# Sheet1.net
KiCad netlist of a schematic drawn in Altium Designer
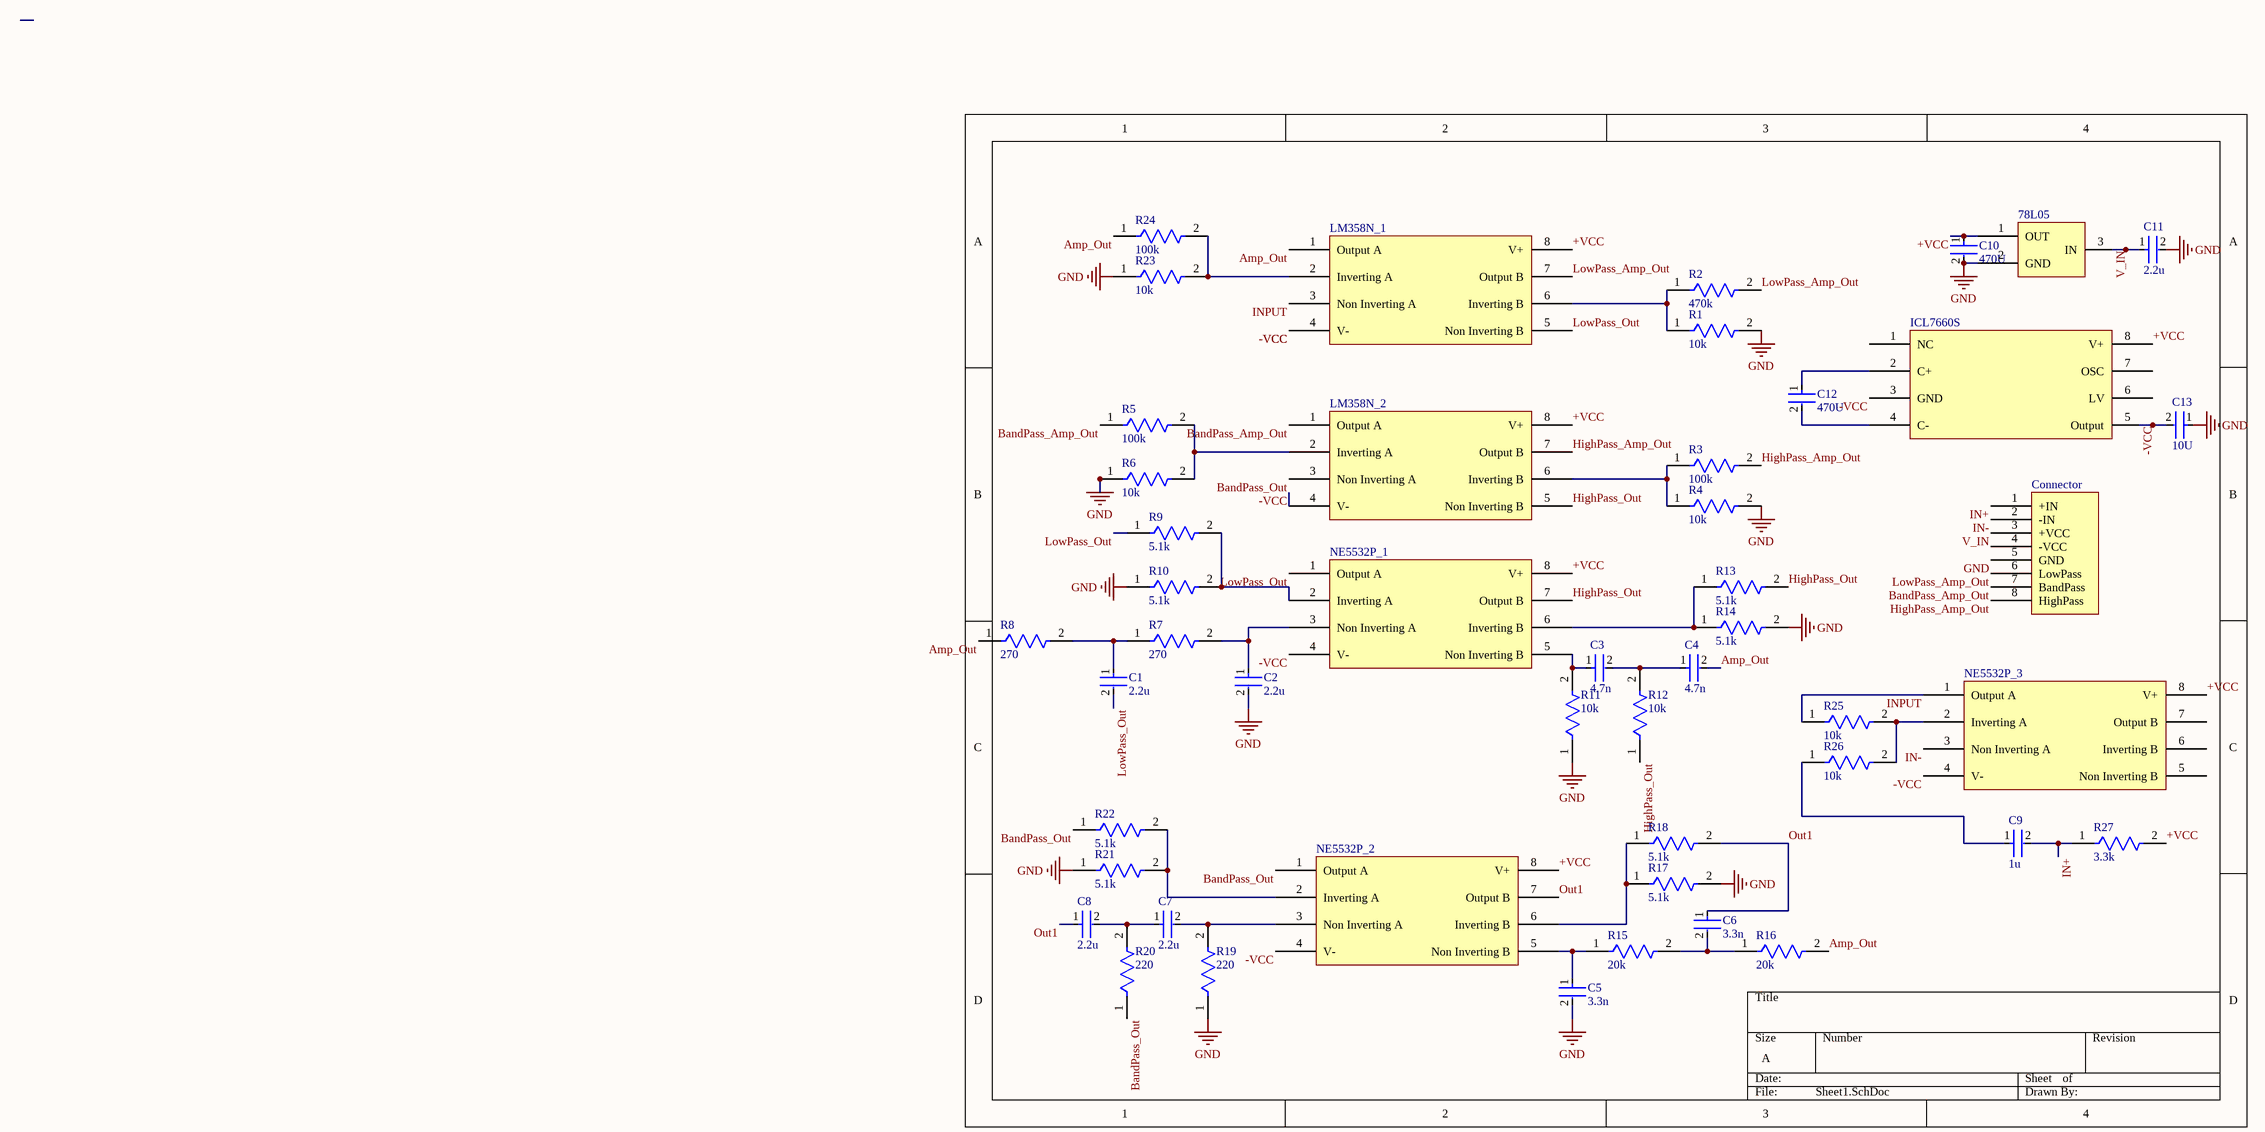
[diagram p0: Sheet1.SchDoc]

(export (version "E")
  (design (tool "Eeschema 10.0.6"))
  (components
    (comp (ref "78L05") (value "~") (footprint "78L05") (libsource (lib "Schlib1") (part "78L05")))
    (comp (ref "C1") (value "2.2u") (footprint "2.2u") (libsource (lib "Schlib1") (part "2.2u")))
    (comp (ref "C2") (value "2.2u") (footprint "2.2u") (libsource (lib "Schlib1") (part "2.2u")))
    (comp (ref "C3") (value "4.7n") (footprint "4.7n") (libsource (lib "Schlib1") (part "4.7n")))
    (comp (ref "C4") (value "4.7n") (footprint "4.7n") (libsource (lib "Schlib1") (part "4.7n")))
    (comp (ref "C5") (value "3.3n") (footprint "4.7n") (libsource (lib "Schlib1") (part "3.3n")))
    (comp (ref "C6") (value "3.3n") (footprint "4.7n") (libsource (lib "Schlib1") (part "3.3n")))
    (comp (ref "C7") (value "2.2u") (footprint "2.2u") (libsource (lib "Schlib1") (part "2.2u")))
    (comp (ref "C8") (value "2.2u") (footprint "2.2u") (libsource (lib "Schlib1") (part "2.2u")))
    (comp (ref "C9") (value "1u") (footprint "1u") (libsource (lib "Schlib1") (part "1u")))
    (comp (ref "C10") (value "470U") (footprint "470u") (libsource (lib "Schlib1") (part "470U")))
    (comp (ref "C11") (value "2.2u") (footprint "2.2u") (libsource (lib "Schlib1") (part "2.2u")))
    (comp (ref "C12") (value "470U") (footprint "470u") (libsource (lib "Schlib1") (part "470U")))
    (comp (ref "C13") (value "10U") (footprint "10u") (libsource (lib "Schlib1") (part "10U")))
    (comp (ref "Connector")
      (value "~")
      (footprint "Connector")
      (libsource (lib "Schlib1") (part "Connector"))
    )
    (comp (ref "ICL7660S") (value "~") (footprint "ICL7660S") (libsource (lib "Schlib1") (part "ICL7660S")))
    (comp (ref "LM358N_1") (value "~") (footprint "LM358N") (libsource (lib "Schlib1") (part "LM358N")))
    (comp (ref "LM358N_2") (value "~") (footprint "LM358N") (libsource (lib "Schlib1") (part "LM358N")))
    (comp (ref "NE5532P_1") (value "~") (footprint "NE5532P") (libsource (lib "Schlib1") (part "NE5532P")))
    (comp (ref "NE5532P_2") (value "~") (footprint "NE5532P") (libsource (lib "Schlib1") (part "NE5532P")))
    (comp (ref "NE5532P_3") (value "~") (footprint "NE5532P") (libsource (lib "Schlib1") (part "NE5532P")))
    (comp (ref "R1") (value "10k") (footprint "THT") (libsource (lib "Schlib1") (part "10k")))
    (comp (ref "R2") (value "470k") (footprint "THT") (libsource (lib "Schlib1") (part "470k")))
    (comp (ref "R3") (value "100k") (footprint "THT") (libsource (lib "Schlib1") (part "100k")))
    (comp (ref "R4") (value "10k") (footprint "THT") (libsource (lib "Schlib1") (part "10k")))
    (comp (ref "R5") (value "100k") (footprint "THT") (libsource (lib "Schlib1") (part "100k")))
    (comp (ref "R6") (value "10k") (footprint "THT") (libsource (lib "Schlib1") (part "10k")))
    (comp (ref "R7") (value "270") (footprint "THT") (libsource (lib "Schlib1") (part "270")))
    (comp (ref "R8") (value "270") (footprint "THT") (libsource (lib "Schlib1") (part "270")))
    (comp (ref "R9") (value "5.1k") (footprint "THT") (libsource (lib "Schlib1") (part "5.1k")))
    (comp (ref "R10") (value "5.1k") (footprint "THT") (libsource (lib "Schlib1") (part "5.1k")))
    (comp (ref "R11") (value "10k") (footprint "THT") (libsource (lib "Schlib1") (part "10k")))
    (comp (ref "R12") (value "10k") (footprint "THT") (libsource (lib "Schlib1") (part "10k")))
    (comp (ref "R13") (value "5.1k") (footprint "THT") (libsource (lib "Schlib1") (part "5.1k")))
    (comp (ref "R14") (value "5.1k") (footprint "THT") (libsource (lib "Schlib1") (part "5.1k")))
    (comp (ref "R15") (value "20k") (footprint "THT") (libsource (lib "Schlib1") (part "20k")))
    (comp (ref "R16") (value "20k") (footprint "THT") (libsource (lib "Schlib1") (part "20k")))
    (comp (ref "R17") (value "5.1k") (footprint "THT") (libsource (lib "Schlib1") (part "5.1k")))
    (comp (ref "R18") (value "5.1k") (footprint "THT") (libsource (lib "Schlib1") (part "5.1k")))
    (comp (ref "R19") (value "220") (footprint "THT") (libsource (lib "Schlib1") (part "220")))
    (comp (ref "R20") (value "220") (footprint "THT") (libsource (lib "Schlib1") (part "220")))
    (comp (ref "R21") (value "5.1k") (footprint "THT") (libsource (lib "Schlib1") (part "5.1k")))
    (comp (ref "R22") (value "5.1k") (footprint "THT") (libsource (lib "Schlib1") (part "5.1k")))
    (comp (ref "R23") (value "10k") (footprint "THT") (libsource (lib "Schlib1") (part "10k")))
    (comp (ref "R24") (value "100k") (footprint "THT") (libsource (lib "Schlib1") (part "100k")))
    (comp (ref "R25") (value "10k") (footprint "THT") (libsource (lib "Schlib1") (part "10k")))
    (comp (ref "R26") (value "10k") (footprint "THT") (libsource (lib "Schlib1") (part "10k")))
    (comp (ref "R27") (value "3.3k") (footprint "THT") (libsource (lib "Schlib1") (part "3.3k")))
  )
  (nets
    (net (code "1") (name "/+VCC") (class "Default")
      (node (ref "78L05") (pin "1") (pinfunction "OUT_1") (pintype "passive"))
      (node (ref "C10") (pin "1") (pinfunction "1_1") (pintype "passive"))
      (node (ref "ICL7660S") (pin "8") (pinfunction "V+_8") (pintype "passive"))
      (node (ref "LM358N_1") (pin "8") (pinfunction "V+_8") (pintype "passive"))
      (node (ref "LM358N_2") (pin "8") (pinfunction "V+_8") (pintype "passive"))
      (node (ref "NE5532P_1") (pin "8") (pinfunction "V+_8") (pintype "passive"))
      (node (ref "NE5532P_2") (pin "8") (pinfunction "V+_8") (pintype "passive"))
      (node (ref "NE5532P_3") (pin "8") (pinfunction "V+_8") (pintype "passive"))
      (node (ref "R27") (pin "2") (pinfunction "2_2") (pintype "passive"))
    )
    (net (code "2") (name "/-VCC") (class "Default")
      (node (ref "C13") (pin "2") (pinfunction "2_2") (pintype "passive"))
      (node (ref "ICL7660S") (pin "3") (pinfunction "GND_3") (pintype "passive"))
      (node (ref "ICL7660S") (pin "5") (pinfunction "Output_5") (pintype "passive"))
      (node (ref "LM358N_1") (pin "4") (pinfunction "V-_4") (pintype "passive"))
      (node (ref "LM358N_2") (pin "4") (pinfunction "V-_4") (pintype "passive"))
      (node (ref "NE5532P_1") (pin "4") (pinfunction "V-_4") (pintype "passive"))
      (node (ref "NE5532P_2") (pin "4") (pinfunction "V-_4") (pintype "passive"))
      (node (ref "NE5532P_3") (pin "4") (pinfunction "V-_4") (pintype "passive"))
    )
    (net (code "3") (name "/Amp_Out") (class "Default")
      (node (ref "C4") (pin "2") (pinfunction "2_2") (pintype "passive"))
      (node (ref "LM358N_1") (pin "1") (pinfunction "Output_A_1") (pintype "passive"))
      (node (ref "R16") (pin "2") (pinfunction "2_2") (pintype "passive"))
      (node (ref "R24") (pin "1") (pinfunction "1_1") (pintype "passive"))
      (node (ref "R8") (pin "1") (pinfunction "1_1") (pintype "passive"))
    )
    (net (code "4") (name "/BandPass_Amp_Out") (class "Default")
      (node (ref "Connector") (pin "7") (pinfunction "BandPass_7") (pintype "passive"))
      (node (ref "LM358N_2") (pin "1") (pinfunction "Output_A_1") (pintype "passive"))
      (node (ref "R5") (pin "1") (pinfunction "1_1") (pintype "passive"))
    )
    (net (code "5") (name "/BandPass_Out") (class "Default")
      (node (ref "LM358N_2") (pin "3") (pinfunction "Non_Inverting_A_3") (pintype "passive"))
      (node (ref "NE5532P_2") (pin "1") (pinfunction "Output_A_1") (pintype "passive"))
      (node (ref "R20") (pin "1") (pinfunction "1_1") (pintype "passive"))
      (node (ref "R22") (pin "1") (pinfunction "1_1") (pintype "passive"))
    )
    (net (code "6") (name "/HighPass_Amp_Out") (class "Default")
      (node (ref "Connector") (pin "8") (pinfunction "HighPass_8") (pintype "passive"))
      (node (ref "LM358N_2") (pin "7") (pinfunction "Output_B_7") (pintype "passive"))
      (node (ref "R3") (pin "2") (pinfunction "2_2") (pintype "passive"))
    )
    (net (code "7") (name "/HighPass_Out") (class "Default")
      (node (ref "LM358N_2") (pin "5") (pinfunction "Non_Inverting_B_5") (pintype "passive"))
      (node (ref "NE5532P_1") (pin "7") (pinfunction "Output_B_7") (pintype "passive"))
      (node (ref "R12") (pin "1") (pinfunction "1_1") (pintype "passive"))
      (node (ref "R13") (pin "2") (pinfunction "2_2") (pintype "passive"))
    )
    (net (code "8") (name "/IN+") (class "Default")
      (node (ref "C9") (pin "2") (pinfunction "2_2") (pintype "passive"))
      (node (ref "Connector") (pin "1") (pinfunction "+IN_1") (pintype "passive"))
      (node (ref "R27") (pin "1") (pinfunction "1_1") (pintype "passive"))
    )
    (net (code "9") (name "/IN-") (class "Default")
      (node (ref "Connector") (pin "2") (pinfunction "-IN_2") (pintype "passive"))
      (node (ref "NE5532P_3") (pin "3") (pinfunction "Non_Inverting_A_3") (pintype "passive"))
    )
    (net (code "10") (name "/INPUT") (class "Default")
      (node (ref "LM358N_1") (pin "3") (pinfunction "Non_Inverting_A_3") (pintype "passive"))
      (node (ref "NE5532P_3") (pin "1") (pinfunction "Output_A_1") (pintype "passive"))
      (node (ref "R25") (pin "1") (pinfunction "1_1") (pintype "passive"))
    )
    (net (code "11") (name "/LowPass_Amp_Out") (class "Default")
      (node (ref "Connector") (pin "6") (pinfunction "LowPass_6") (pintype "passive"))
      (node (ref "LM358N_1") (pin "7") (pinfunction "Output_B_7") (pintype "passive"))
      (node (ref "R2") (pin "2") (pinfunction "2_2") (pintype "passive"))
    )
    (net (code "12") (name "/LowPass_Out") (class "Default")
      (node (ref "C1") (pin "2") (pinfunction "2_2") (pintype "passive"))
      (node (ref "LM358N_1") (pin "5") (pinfunction "Non_Inverting_B_5") (pintype "passive"))
      (node (ref "NE5532P_1") (pin "1") (pinfunction "Output_A_1") (pintype "passive"))
      (node (ref "R9") (pin "1") (pinfunction "1_1") (pintype "passive"))
    )
    (net (code "13") (name "/Out1") (class "Default")
      (node (ref "C6") (pin "1") (pinfunction "1_1") (pintype "passive"))
      (node (ref "C8") (pin "1") (pinfunction "1_1") (pintype "passive"))
      (node (ref "NE5532P_2") (pin "7") (pinfunction "Output_B_7") (pintype "passive"))
      (node (ref "R18") (pin "2") (pinfunction "2_2") (pintype "passive"))
    )
    (net (code "14") (name "/V_IN") (class "Default")
      (node (ref "78L05") (pin "3") (pinfunction "IN_3") (pintype "passive"))
      (node (ref "C11") (pin "1") (pinfunction "1_1") (pintype "passive"))
      (node (ref "Connector") (pin "3") (pinfunction "+VCC_3") (pintype "passive"))
    )
    (net (code "15") (name "GND") (class "Default")
      (node (ref "78L05") (pin "2") (pinfunction "GND_2") (pintype "passive"))
      (node (ref "C10") (pin "2") (pinfunction "2_2") (pintype "passive"))
      (node (ref "C11") (pin "2") (pinfunction "2_2") (pintype "passive"))
      (node (ref "C13") (pin "1") (pinfunction "1_1") (pintype "passive"))
      (node (ref "C2") (pin "2") (pinfunction "2_2") (pintype "passive"))
      (node (ref "C5") (pin "2") (pinfunction "2_2") (pintype "passive"))
      (node (ref "Connector") (pin "5") (pinfunction "GND_5") (pintype "passive"))
      (node (ref "R1") (pin "2") (pinfunction "2_2") (pintype "passive"))
      (node (ref "R10") (pin "1") (pinfunction "1_1") (pintype "passive"))
      (node (ref "R11") (pin "1") (pinfunction "1_1") (pintype "passive"))
      (node (ref "R14") (pin "2") (pinfunction "2_2") (pintype "passive"))
      (node (ref "R17") (pin "2") (pinfunction "2_2") (pintype "passive"))
      (node (ref "R19") (pin "1") (pinfunction "1_1") (pintype "passive"))
      (node (ref "R21") (pin "1") (pinfunction "1_1") (pintype "passive"))
      (node (ref "R23") (pin "1") (pinfunction "1_1") (pintype "passive"))
      (node (ref "R4") (pin "2") (pinfunction "2_2") (pintype "passive"))
      (node (ref "R6") (pin "1") (pinfunction "1_1") (pintype "passive"))
    )
    (net (code "16") (name "Net-(C1-Pad1)") (class "Default")
      (node (ref "C1") (pin "1") (pinfunction "1_1") (pintype "passive"))
      (node (ref "R7") (pin "1") (pinfunction "1_1") (pintype "passive"))
      (node (ref "R8") (pin "2") (pinfunction "2_2") (pintype "passive"))
    )
    (net (code "17") (name "Net-(C3-Pad2)") (class "Default")
      (node (ref "C3") (pin "2") (pinfunction "2_2") (pintype "passive"))
      (node (ref "C4") (pin "1") (pinfunction "1_1") (pintype "passive"))
      (node (ref "R12") (pin "2") (pinfunction "2_2") (pintype "passive"))
    )
    (net (code "18") (name "Net-(C6-Pad2)") (class "Default")
      (node (ref "C6") (pin "2") (pinfunction "2_2") (pintype "passive"))
      (node (ref "R15") (pin "2") (pinfunction "2_2") (pintype "passive"))
      (node (ref "R16") (pin "1") (pinfunction "1_1") (pintype "passive"))
    )
    (net (code "19") (name "Net-(C7-Pad1)") (class "Default")
      (node (ref "C7") (pin "1") (pinfunction "1_1") (pintype "passive"))
      (node (ref "C8") (pin "2") (pinfunction "2_2") (pintype "passive"))
      (node (ref "R20") (pin "2") (pinfunction "2_2") (pintype "passive"))
    )
    (net (code "20") (name "Net-(C9-Pad1)") (class "Default")
      (node (ref "C9") (pin "1") (pinfunction "1_1") (pintype "passive"))
      (node (ref "R26") (pin "1") (pinfunction "1_1") (pintype "passive"))
    )
    (net (code "21") (name "Net-(ICL7660S-C+)") (class "Default")
      (node (ref "C12") (pin "1") (pinfunction "1_1") (pintype "passive"))
      (node (ref "ICL7660S") (pin "2") (pinfunction "C+_2") (pintype "passive"))
    )
    (net (code "22") (name "Net-(ICL7660S-C-)") (class "Default")
      (node (ref "C12") (pin "2") (pinfunction "2_2") (pintype "passive"))
      (node (ref "ICL7660S") (pin "4") (pinfunction "C-_4") (pintype "passive"))
    )
    (net (code "23") (name "Net-(LM358N_1-Inverting_A)") (class "Default")
      (node (ref "LM358N_1") (pin "2") (pinfunction "Inverting_A_2") (pintype "passive"))
      (node (ref "R23") (pin "2") (pinfunction "2_2") (pintype "passive"))
      (node (ref "R24") (pin "2") (pinfunction "2_2") (pintype "passive"))
    )
    (net (code "24") (name "Net-(LM358N_1-Inverting_B)") (class "Default")
      (node (ref "LM358N_1") (pin "6") (pinfunction "Inverting_B_6") (pintype "passive"))
      (node (ref "R1") (pin "1") (pinfunction "1_1") (pintype "passive"))
      (node (ref "R2") (pin "1") (pinfunction "1_1") (pintype "passive"))
    )
    (net (code "25") (name "Net-(LM358N_2-Inverting_A)") (class "Default")
      (node (ref "LM358N_2") (pin "2") (pinfunction "Inverting_A_2") (pintype "passive"))
      (node (ref "R5") (pin "2") (pinfunction "2_2") (pintype "passive"))
      (node (ref "R6") (pin "2") (pinfunction "2_2") (pintype "passive"))
    )
    (net (code "26") (name "Net-(LM358N_2-Inverting_B)") (class "Default")
      (node (ref "LM358N_2") (pin "6") (pinfunction "Inverting_B_6") (pintype "passive"))
      (node (ref "R3") (pin "1") (pinfunction "1_1") (pintype "passive"))
      (node (ref "R4") (pin "1") (pinfunction "1_1") (pintype "passive"))
    )
    (net (code "27") (name "Net-(NE5532P_1-Inverting_A)") (class "Default")
      (node (ref "NE5532P_1") (pin "2") (pinfunction "Inverting_A_2") (pintype "passive"))
      (node (ref "R10") (pin "2") (pinfunction "2_2") (pintype "passive"))
      (node (ref "R9") (pin "2") (pinfunction "2_2") (pintype "passive"))
    )
    (net (code "28") (name "Net-(NE5532P_1-Inverting_B)") (class "Default")
      (node (ref "NE5532P_1") (pin "6") (pinfunction "Inverting_B_6") (pintype "passive"))
      (node (ref "R13") (pin "1") (pinfunction "1_1") (pintype "passive"))
      (node (ref "R14") (pin "1") (pinfunction "1_1") (pintype "passive"))
    )
    (net (code "29") (name "Net-(NE5532P_1-Non_Inverting_A)") (class "Default")
      (node (ref "C2") (pin "1") (pinfunction "1_1") (pintype "passive"))
      (node (ref "NE5532P_1") (pin "3") (pinfunction "Non_Inverting_A_3") (pintype "passive"))
      (node (ref "R7") (pin "2") (pinfunction "2_2") (pintype "passive"))
    )
    (net (code "30") (name "Net-(NE5532P_1-Non_Inverting_B)") (class "Default")
      (node (ref "C3") (pin "1") (pinfunction "1_1") (pintype "passive"))
      (node (ref "NE5532P_1") (pin "5") (pinfunction "Non_Inverting_B_5") (pintype "passive"))
      (node (ref "R11") (pin "2") (pinfunction "2_2") (pintype "passive"))
    )
    (net (code "31") (name "Net-(NE5532P_2-Inverting_A)") (class "Default")
      (node (ref "NE5532P_2") (pin "2") (pinfunction "Inverting_A_2") (pintype "passive"))
      (node (ref "R21") (pin "2") (pinfunction "2_2") (pintype "passive"))
      (node (ref "R22") (pin "2") (pinfunction "2_2") (pintype "passive"))
    )
    (net (code "32") (name "Net-(NE5532P_2-Inverting_B)") (class "Default")
      (node (ref "NE5532P_2") (pin "6") (pinfunction "Inverting_B_6") (pintype "passive"))
      (node (ref "R17") (pin "1") (pinfunction "1_1") (pintype "passive"))
      (node (ref "R18") (pin "1") (pinfunction "1_1") (pintype "passive"))
    )
    (net (code "33") (name "Net-(NE5532P_2-Non_Inverting_A)") (class "Default")
      (node (ref "C7") (pin "2") (pinfunction "2_2") (pintype "passive"))
      (node (ref "NE5532P_2") (pin "3") (pinfunction "Non_Inverting_A_3") (pintype "passive"))
      (node (ref "R19") (pin "2") (pinfunction "2_2") (pintype "passive"))
    )
    (net (code "34") (name "Net-(NE5532P_2-Non_Inverting_B)") (class "Default")
      (node (ref "C5") (pin "1") (pinfunction "1_1") (pintype "passive"))
      (node (ref "NE5532P_2") (pin "5") (pinfunction "Non_Inverting_B_5") (pintype "passive"))
      (node (ref "R15") (pin "1") (pinfunction "1_1") (pintype "passive"))
    )
    (net (code "35") (name "Net-(NE5532P_3-Inverting_A)") (class "Default")
      (node (ref "NE5532P_3") (pin "2") (pinfunction "Inverting_A_2") (pintype "passive"))
      (node (ref "R25") (pin "2") (pinfunction "2_2") (pintype "passive"))
      (node (ref "R26") (pin "2") (pinfunction "2_2") (pintype "passive"))
    )
    (net (code "36") (name "unconnected-(Connector--VCC-Pad4)") (class "Default")
      (node (ref "Connector") (pin "4") (pinfunction "-VCC_4") (pintype "passive"))
    )
    (net (code "37") (name "unconnected-(ICL7660S-LV-Pad6)") (class "Default")
      (node (ref "ICL7660S") (pin "6") (pinfunction "LV_6") (pintype "passive"))
    )
    (net (code "38") (name "unconnected-(ICL7660S-NC-Pad1)") (class "Default")
      (node (ref "ICL7660S") (pin "1") (pinfunction "NC_1") (pintype "passive"))
    )
    (net (code "39") (name "unconnected-(ICL7660S-OSC-Pad7)") (class "Default")
      (node (ref "ICL7660S") (pin "7") (pinfunction "OSC_7") (pintype "passive"))
    )
    (net (code "40") (name "unconnected-(NE5532P_3-Inverting_B-Pad6)") (class "Default")
      (node (ref "NE5532P_3") (pin "6") (pinfunction "Inverting_B_6") (pintype "passive"))
    )
    (net (code "41") (name "unconnected-(NE5532P_3-Non_Inverting_B-Pad5)") (class "Default")
      (node (ref "NE5532P_3") (pin "5") (pinfunction "Non_Inverting_B_5") (pintype "passive"))
    )
    (net (code "42") (name "unconnected-(NE5532P_3-Output_B-Pad7)") (class "Default")
      (node (ref "NE5532P_3") (pin "7") (pinfunction "Output_B_7") (pintype "passive"))
    )
  )
)
